# platform_smd2.net
KiCad netlist of a schematic drawn in EAGLE
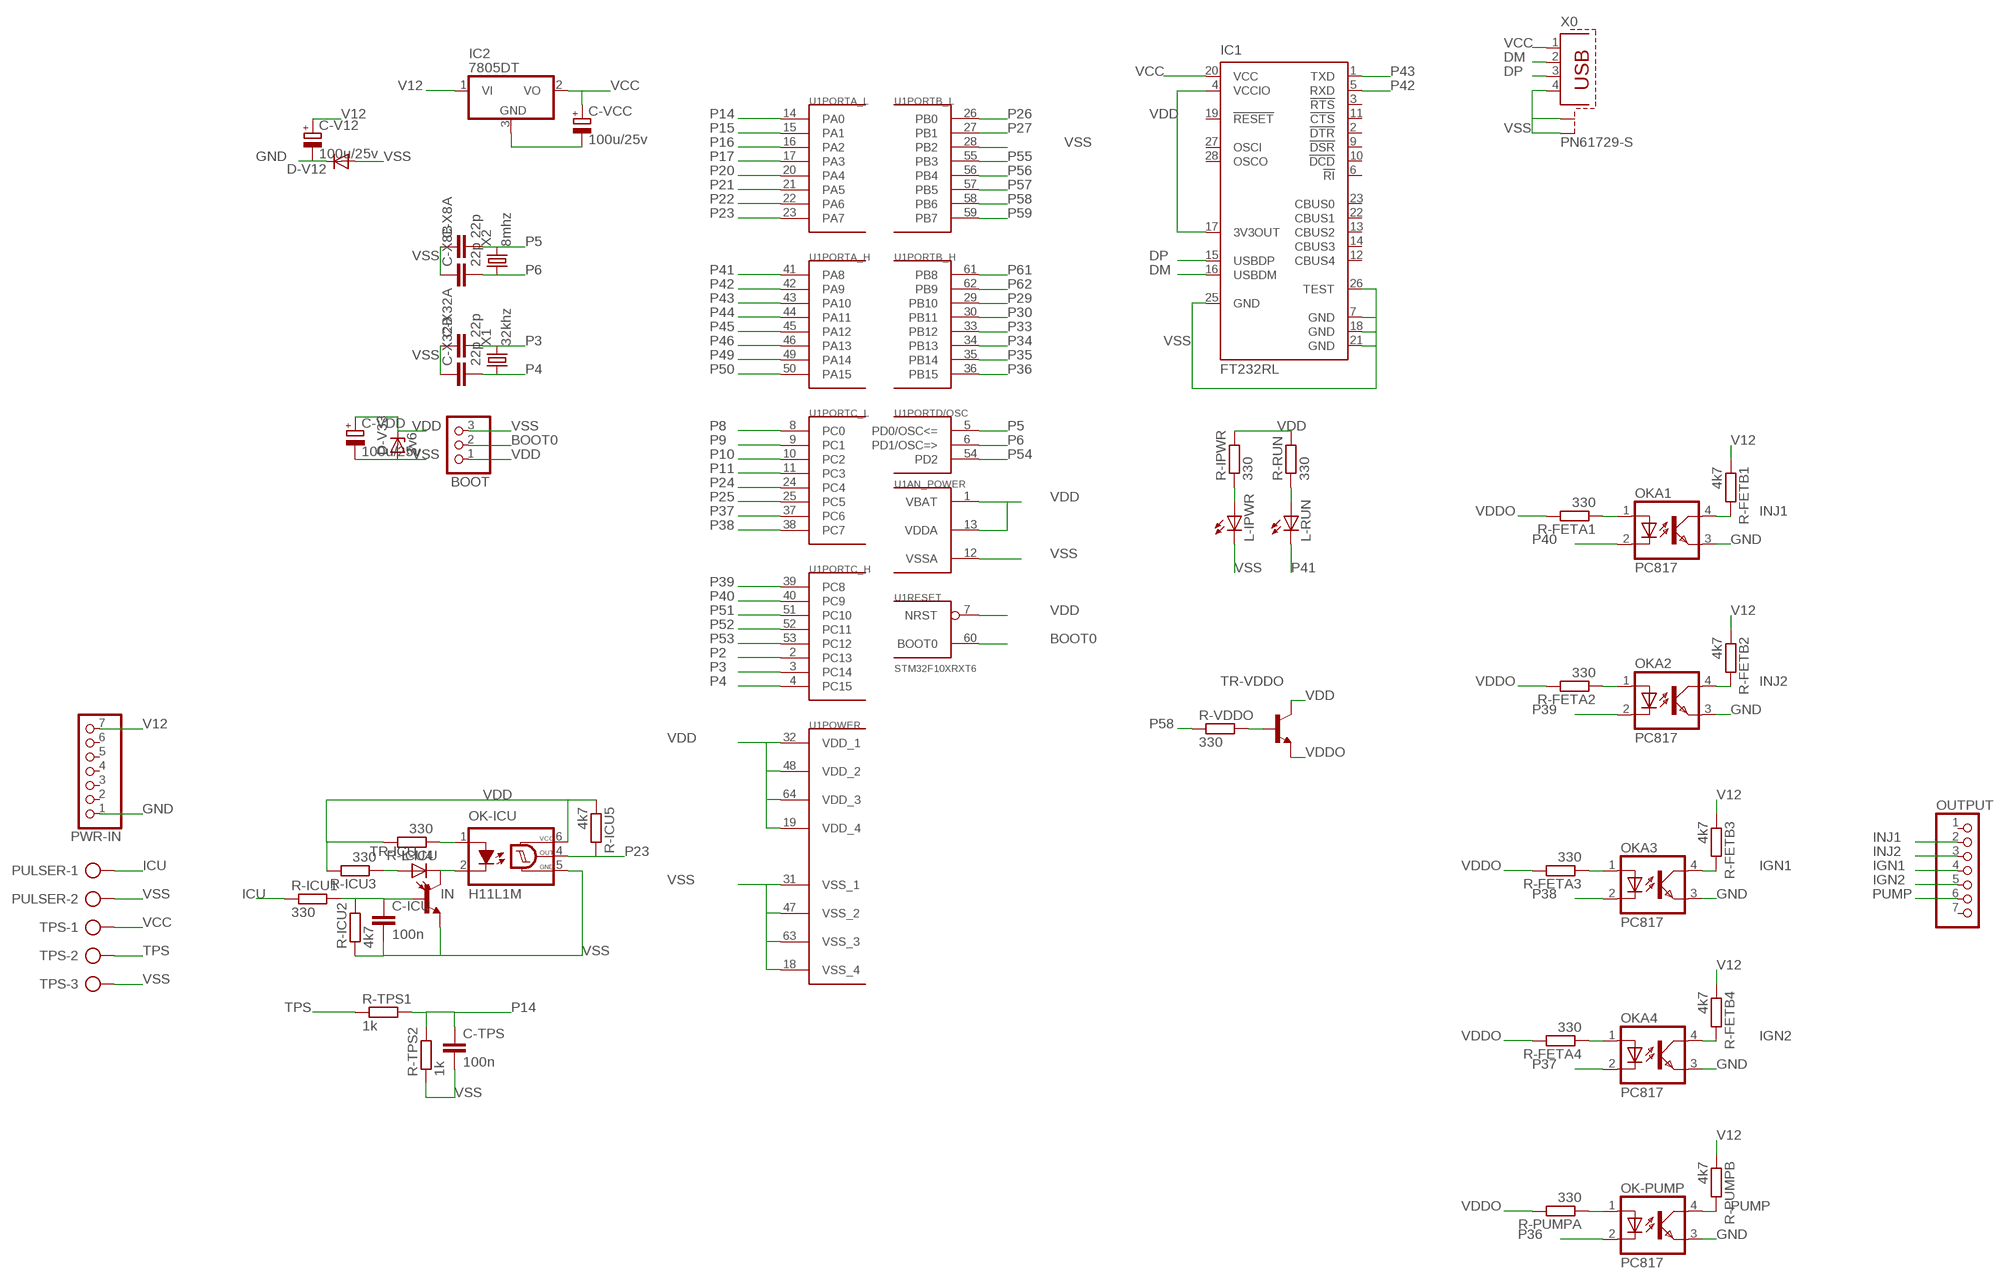
[diagram p0: schematic, sheet 1]

(export (version "E")
  (design (tool "Eeschema 10.0.6"))
  (components
    (comp (ref "BOOT")
      (value "PINHD-1X3")
      (footprint "eagle-import:1X03")
      (libsource (lib "eagle-import") (part "PINHD-1X3"))
    )
    (comp (ref "C-ICU")
      (value "100n")
      (footprint "eagle-import:C1206")
      (libsource (lib "eagle-import") (part "C-EUC1206"))
    )
    (comp (ref "C-TPS")
      (value "100n")
      (footprint "eagle-import:C1206")
      (libsource (lib "eagle-import") (part "C-EUC1206"))
    )
    (comp (ref "C-V12")
      (value "100u/25v")
      (footprint "eagle-import:PANASONIC_D")
      (libsource (lib "eagle-import") (part "CPOL-EUD"))
    )
    (comp (ref "C-VCC")
      (value "100u/25v")
      (footprint "eagle-import:PANASONIC_D")
      (libsource (lib "eagle-import") (part "CPOL-EUD"))
    )
    (comp (ref "C-VDD")
      (value "100u/25v")
      (footprint "eagle-import:PANASONIC_D")
      (libsource (lib "eagle-import") (part "CPOL-EUD"))
    )
    (comp (ref "C-X8A")
      (value "22p")
      (footprint "eagle-import:C1206")
      (libsource (lib "eagle-import") (part "C-EUC1206"))
    )
    (comp (ref "C-X8B")
      (value "22p")
      (footprint "eagle-import:C1206")
      (libsource (lib "eagle-import") (part "C-EUC1206"))
    )
    (comp (ref "C-X32A")
      (value "22p")
      (footprint "eagle-import:C1206")
      (libsource (lib "eagle-import") (part "C-EUC1206"))
    )
    (comp (ref "C-X32B")
      (value "22p")
      (footprint "eagle-import:C1206")
      (libsource (lib "eagle-import") (part "C-EUC1206"))
    )
    (comp (ref "D-V12")
      (value "DIODE-SMB")
      (footprint "eagle-import:SMB")
      (libsource (lib "eagle-import") (part "DIODE-SMB"))
    )
    (comp (ref "D-V33")
      (value "3v6")
      (footprint "eagle-import:SMB")
      (libsource (lib "eagle-import") (part "ZENER-DIODESMB"))
    )
    (comp (ref "IC1")
      (value "FT232RL")
      (footprint "eagle-import:SSOP28")
      (libsource (lib "eagle-import") (part "FT232RL"))
    )
    (comp (ref "IC2")
      (value "7805DT")
      (footprint "eagle-import:TO252")
      (libsource (lib "eagle-import") (part "78DT05"))
    )
    (comp (ref "L-ICU")
      (value "LEDSML0805")
      (footprint "eagle-import:SML0805")
      (libsource (lib "eagle-import") (part "LEDSML0805"))
    )
    (comp (ref "L-IPWR")
      (value "LEDSMT1206")
      (footprint "eagle-import:1206")
      (libsource (lib "eagle-import") (part "LEDSMT1206"))
    )
    (comp (ref "L-RUN")
      (value "LEDSMT1206")
      (footprint "eagle-import:1206")
      (libsource (lib "eagle-import") (part "LEDSMT1206"))
    )
    (comp (ref "OK-ICU")
      (value "H11L1M")
      (footprint "eagle-import:DIL06")
      (fields (field (name "MF") "FAIRCHILD SEMICONDUCTOR") (field (name "MPN") "H11L1-M"))
      (libsource (lib "eagle-import") (part "H11LM1"))
    )
    (comp (ref "OK-PUMP")
      (value "PC817")
      (footprint "eagle-import:DIL04")
      (fields (field (name "MPN") "PC817X4J000F"))
      (libsource (lib "eagle-import") (part "PC817"))
    )
    (comp (ref "OKA1")
      (value "PC817")
      (footprint "eagle-import:DIL04")
      (fields (field (name "MPN") "PC817X4J000F"))
      (libsource (lib "eagle-import") (part "PC817"))
    )
    (comp (ref "OKA2")
      (value "PC817")
      (footprint "eagle-import:DIL04")
      (fields (field (name "MPN") "PC817X4J000F"))
      (libsource (lib "eagle-import") (part "PC817"))
    )
    (comp (ref "OKA3")
      (value "PC817")
      (footprint "eagle-import:DIL04")
      (fields (field (name "MPN") "PC817X4J000F"))
      (libsource (lib "eagle-import") (part "PC817"))
    )
    (comp (ref "OKA4")
      (value "PC817")
      (footprint "eagle-import:DIL04")
      (fields (field (name "MPN") "PC817X4J000F"))
      (libsource (lib "eagle-import") (part "PC817"))
    )
    (comp (ref "OUTPUT")
      (value "PINHD-1X7")
      (footprint "eagle-import:1X07")
      (libsource (lib "eagle-import") (part "PINHD-1X7"))
    )
    (comp (ref "PULSER")
      (value "AK300/2")
      (footprint "eagle-import:AK300_2")
      (libsource (lib "eagle-import") (part "AK300/2"))
    )
    (comp (ref "PWR-IN")
      (value "PINHD-1X7")
      (footprint "eagle-import:1X07")
      (libsource (lib "eagle-import") (part "PINHD-1X7"))
    )
    (comp (ref "R-FETA1")
      (value "330")
      (footprint "eagle-import:R1206")
      (libsource (lib "eagle-import") (part "R-EU_R1206"))
    )
    (comp (ref "R-FETA2")
      (value "330")
      (footprint "eagle-import:R1206")
      (libsource (lib "eagle-import") (part "R-EU_R1206"))
    )
    (comp (ref "R-FETA3")
      (value "330")
      (footprint "eagle-import:R1206")
      (libsource (lib "eagle-import") (part "R-EU_R1206"))
    )
    (comp (ref "R-FETA4")
      (value "330")
      (footprint "eagle-import:R1206")
      (libsource (lib "eagle-import") (part "R-EU_R1206"))
    )
    (comp (ref "R-FETB1")
      (value "4k7")
      (footprint "eagle-import:R1206")
      (libsource (lib "eagle-import") (part "R-EU_R1206"))
    )
    (comp (ref "R-FETB2")
      (value "4k7")
      (footprint "eagle-import:R1206")
      (libsource (lib "eagle-import") (part "R-EU_R1206"))
    )
    (comp (ref "R-FETB3")
      (value "4k7")
      (footprint "eagle-import:R1206")
      (libsource (lib "eagle-import") (part "R-EU_R1206"))
    )
    (comp (ref "R-FETB4")
      (value "4k7")
      (footprint "eagle-import:R1206")
      (libsource (lib "eagle-import") (part "R-EU_R1206"))
    )
    (comp (ref "R-ICU1")
      (value "330")
      (footprint "eagle-import:R1206")
      (libsource (lib "eagle-import") (part "R-EU_R1206"))
    )
    (comp (ref "R-ICU2")
      (value "4k7")
      (footprint "eagle-import:R1206")
      (libsource (lib "eagle-import") (part "R-EU_R1206"))
    )
    (comp (ref "R-ICU3")
      (value "330")
      (footprint "eagle-import:R1206")
      (libsource (lib "eagle-import") (part "R-EU_R1206"))
    )
    (comp (ref "R-ICU4")
      (value "330")
      (footprint "eagle-import:R1206")
      (libsource (lib "eagle-import") (part "R-EU_R1206"))
    )
    (comp (ref "R-ICU5")
      (value "4k7")
      (footprint "eagle-import:R1206")
      (libsource (lib "eagle-import") (part "R-EU_R1206"))
    )
    (comp (ref "R-IPWR")
      (value "330")
      (footprint "eagle-import:R1206")
      (libsource (lib "eagle-import") (part "R-EU_R1206"))
    )
    (comp (ref "R-PUMPA")
      (value "330")
      (footprint "eagle-import:R1206")
      (libsource (lib "eagle-import") (part "R-EU_R1206"))
    )
    (comp (ref "R-PUMPB")
      (value "4k7")
      (footprint "eagle-import:R1206")
      (libsource (lib "eagle-import") (part "R-EU_R1206"))
    )
    (comp (ref "R-RUN")
      (value "330")
      (footprint "eagle-import:R1206")
      (libsource (lib "eagle-import") (part "R-EU_R1206"))
    )
    (comp (ref "R-TPS1")
      (value "1k")
      (footprint "eagle-import:R1206")
      (libsource (lib "eagle-import") (part "R-EU_R1206"))
    )
    (comp (ref "R-TPS2")
      (value "1k")
      (footprint "eagle-import:R1206")
      (libsource (lib "eagle-import") (part "R-EU_R1206"))
    )
    (comp (ref "R-VDDO")
      (value "330")
      (footprint "eagle-import:R0805")
      (libsource (lib "eagle-import") (part "R-EU_R0805"))
    )
    (comp (ref "TPS")
      (value "AK300/3")
      (footprint "eagle-import:AK300_3")
      (libsource (lib "eagle-import") (part "AK300/3"))
    )
    (comp (ref "TR-ICU")
      (value "MMBT3904LT1-NPN-SOT23-BEC")
      (footprint "eagle-import:SOT23-BEC")
      (libsource (lib "eagle-import") (part "-NPN-SOT23-BECMMBT3904LT1"))
    )
    (comp (ref "TR-VDDO")
      (value "MMBT3904LT1-NPN-SOT23-BEC")
      (footprint "eagle-import:SOT23-BEC")
      (libsource (lib "eagle-import") (part "-NPN-SOT23-BECMMBT3904LT1"))
    )
    (comp (ref "U1")
      (value "STM32F10XRXT6")
      (footprint "eagle-import:TQFP64")
      (libsource (lib "eagle-import") (part "STM32F10XRXT6"))
    )
    (comp (ref "X0")
      (value "PN61729-S")
      (footprint "eagle-import:PN61729-S")
      (libsource (lib "eagle-import") (part "PN61729-S"))
    )
    (comp (ref "X1")
      (value "32khz")
      (footprint "eagle-import:TC26V")
      (libsource (lib "eagle-import") (part "CRYSTALTC26V"))
    )
    (comp (ref "X2")
      (value "8mhz")
      (footprint "eagle-import:HC49U-V")
      (libsource (lib "eagle-import") (part "CRYSTALHC49U-V"))
    )
  )
  (nets
    (net (code "1") (name "/BOOT0") (class "Default")
      (node (ref "BOOT") (pin "2") (pinfunction "2_2") (pintype "passive"))
      (node (ref "U1") (pin "60") (pinfunction "BOOT0_60") (pintype "input"))
    )
    (net (code "2") (name "/DM") (class "Default")
      (node (ref "IC1") (pin "16") (pinfunction "USBDM_16") (pintype "bidirectional"))
      (node (ref "X0") (pin "2") (pinfunction "2_2") (pintype "passive"))
    )
    (net (code "3") (name "/DP") (class "Default")
      (node (ref "IC1") (pin "15") (pinfunction "USBDP_15") (pintype "bidirectional"))
      (node (ref "X0") (pin "3") (pinfunction "3_3") (pintype "passive"))
    )
    (net (code "4") (name "/GND") (class "Default")
      (node (ref "C-V12") (pin "-") (pinfunction "-_-") (pintype "passive"))
      (node (ref "D-V12") (pin "C") (pinfunction "C_C") (pintype "passive"))
      (node (ref "OK-PUMP") (pin "3") (pinfunction "EMIT_3") (pintype "passive"))
      (node (ref "OKA1") (pin "3") (pinfunction "EMIT_3") (pintype "passive"))
      (node (ref "OKA2") (pin "3") (pinfunction "EMIT_3") (pintype "passive"))
      (node (ref "OKA3") (pin "3") (pinfunction "EMIT_3") (pintype "passive"))
      (node (ref "OKA4") (pin "3") (pinfunction "EMIT_3") (pintype "passive"))
      (node (ref "PWR-IN") (pin "1") (pinfunction "1_1") (pintype "passive"))
    )
    (net (code "5") (name "/ICU") (class "Default")
      (node (ref "PULSER") (pin "1") (pinfunction "KL_1") (pintype "passive"))
      (node (ref "R-ICU1") (pin "1") (pinfunction "1_1") (pintype "passive"))
    )
    (net (code "6") (name "/IGN1") (class "Default")
      (node (ref "OKA3") (pin "4") (pinfunction "COL_4") (pintype "passive"))
      (node (ref "OUTPUT") (pin "4") (pinfunction "4_4") (pintype "passive"))
      (node (ref "R-FETB3") (pin "2") (pinfunction "2_2") (pintype "passive"))
    )
    (net (code "7") (name "/IGN2") (class "Default")
      (node (ref "OKA4") (pin "4") (pinfunction "COL_4") (pintype "passive"))
      (node (ref "OUTPUT") (pin "5") (pinfunction "5_5") (pintype "passive"))
      (node (ref "R-FETB4") (pin "2") (pinfunction "2_2") (pintype "passive"))
    )
    (net (code "8") (name "/IN") (class "Default")
      (node (ref "L-ICU") (pin "C") (pinfunction "C_C") (pintype "passive"))
      (node (ref "OK-ICU") (pin "2") (pinfunction "C_2") (pintype "passive"))
      (node (ref "TR-ICU") (pin "C") (pinfunction "C_C") (pintype "passive"))
    )
    (net (code "9") (name "/INJ1") (class "Default")
      (node (ref "OKA1") (pin "4") (pinfunction "COL_4") (pintype "passive"))
      (node (ref "OUTPUT") (pin "2") (pinfunction "2_2") (pintype "passive"))
      (node (ref "R-FETB1") (pin "2") (pinfunction "2_2") (pintype "passive"))
    )
    (net (code "10") (name "/INJ2") (class "Default")
      (node (ref "OKA2") (pin "4") (pinfunction "COL_4") (pintype "passive"))
      (node (ref "OUTPUT") (pin "3") (pinfunction "3_3") (pintype "passive"))
      (node (ref "R-FETB2") (pin "2") (pinfunction "2_2") (pintype "passive"))
    )
    (net (code "11") (name "/P2") (class "Default")
      (node (ref "U1") (pin "2") (pinfunction "PC13_2") (pintype "bidirectional"))
    )
    (net (code "12") (name "/P3") (class "Default")
      (node (ref "C-X32A") (pin "2") (pinfunction "2_2") (pintype "passive"))
      (node (ref "U1") (pin "3") (pinfunction "PC14_3") (pintype "bidirectional"))
      (node (ref "X1") (pin "2") (pinfunction "2_2") (pintype "passive"))
    )
    (net (code "13") (name "/P4") (class "Default")
      (node (ref "C-X32B") (pin "2") (pinfunction "2_2") (pintype "passive"))
      (node (ref "U1") (pin "4") (pinfunction "PC15_4") (pintype "bidirectional"))
      (node (ref "X1") (pin "1") (pinfunction "1_1") (pintype "passive"))
    )
    (net (code "14") (name "/P5") (class "Default")
      (node (ref "C-X8A") (pin "2") (pinfunction "2_2") (pintype "passive"))
      (node (ref "U1") (pin "5") (pinfunction "PD0/OSC<=_5") (pintype "bidirectional"))
      (node (ref "X2") (pin "2") (pinfunction "2_2") (pintype "passive"))
    )
    (net (code "15") (name "/P6") (class "Default")
      (node (ref "C-X8B") (pin "2") (pinfunction "2_2") (pintype "passive"))
      (node (ref "U1") (pin "6") (pinfunction "PD1/OSC=>_6") (pintype "bidirectional"))
      (node (ref "X2") (pin "1") (pinfunction "1_1") (pintype "passive"))
    )
    (net (code "16") (name "/P8") (class "Default")
      (node (ref "U1") (pin "8") (pinfunction "PC0_8") (pintype "bidirectional"))
    )
    (net (code "17") (name "/P9") (class "Default")
      (node (ref "U1") (pin "9") (pinfunction "PC1_9") (pintype "bidirectional"))
    )
    (net (code "18") (name "/P10") (class "Default")
      (node (ref "U1") (pin "10") (pinfunction "PC2_10") (pintype "bidirectional"))
    )
    (net (code "19") (name "/P11") (class "Default")
      (node (ref "U1") (pin "11") (pinfunction "PC3_11") (pintype "bidirectional"))
    )
    (net (code "20") (name "/P14") (class "Default")
      (node (ref "C-TPS") (pin "1") (pinfunction "1_1") (pintype "passive"))
      (node (ref "R-TPS1") (pin "2") (pinfunction "2_2") (pintype "passive"))
      (node (ref "R-TPS2") (pin "2") (pinfunction "2_2") (pintype "passive"))
      (node (ref "U1") (pin "14") (pinfunction "PA0_14") (pintype "bidirectional"))
    )
    (net (code "21") (name "/P15") (class "Default")
      (node (ref "U1") (pin "15") (pinfunction "PA1_15") (pintype "bidirectional"))
    )
    (net (code "22") (name "/P16") (class "Default")
      (node (ref "U1") (pin "16") (pinfunction "PA2_16") (pintype "bidirectional"))
    )
    (net (code "23") (name "/P17") (class "Default")
      (node (ref "U1") (pin "17") (pinfunction "PA3_17") (pintype "bidirectional"))
    )
    (net (code "24") (name "/P20") (class "Default")
      (node (ref "U1") (pin "20") (pinfunction "PA4_20") (pintype "bidirectional"))
    )
    (net (code "25") (name "/P21") (class "Default")
      (node (ref "U1") (pin "21") (pinfunction "PA5_21") (pintype "bidirectional"))
    )
    (net (code "26") (name "/P22") (class "Default")
      (node (ref "U1") (pin "22") (pinfunction "PA6_22") (pintype "bidirectional"))
    )
    (net (code "27") (name "/P23") (class "Default")
      (node (ref "OK-ICU") (pin "4") (pinfunction "OUT_4") (pintype "output"))
      (node (ref "R-ICU5") (pin "2") (pinfunction "2_2") (pintype "passive"))
      (node (ref "U1") (pin "23") (pinfunction "PA7_23") (pintype "bidirectional"))
    )
    (net (code "28") (name "/P24") (class "Default")
      (node (ref "U1") (pin "24") (pinfunction "PC4_24") (pintype "bidirectional"))
    )
    (net (code "29") (name "/P25") (class "Default")
      (node (ref "U1") (pin "25") (pinfunction "PC5_25") (pintype "bidirectional"))
    )
    (net (code "30") (name "/P26") (class "Default")
      (node (ref "U1") (pin "26") (pinfunction "PB0_26") (pintype "bidirectional"))
    )
    (net (code "31") (name "/P27") (class "Default")
      (node (ref "U1") (pin "27") (pinfunction "PB1_27") (pintype "bidirectional"))
    )
    (net (code "32") (name "/P29") (class "Default")
      (node (ref "U1") (pin "29") (pinfunction "PB10_29") (pintype "bidirectional"))
    )
    (net (code "33") (name "/P30") (class "Default")
      (node (ref "U1") (pin "30") (pinfunction "PB11_30") (pintype "bidirectional"))
    )
    (net (code "34") (name "/P33") (class "Default")
      (node (ref "U1") (pin "33") (pinfunction "PB12_33") (pintype "bidirectional"))
    )
    (net (code "35") (name "/P34") (class "Default")
      (node (ref "U1") (pin "34") (pinfunction "PB13_34") (pintype "bidirectional"))
    )
    (net (code "36") (name "/P35") (class "Default")
      (node (ref "U1") (pin "35") (pinfunction "PB14_35") (pintype "bidirectional"))
    )
    (net (code "37") (name "/P36") (class "Default")
      (node (ref "OK-PUMP") (pin "2") (pinfunction "C_2") (pintype "passive"))
      (node (ref "U1") (pin "36") (pinfunction "PB15_36") (pintype "bidirectional"))
    )
    (net (code "38") (name "/P37") (class "Default")
      (node (ref "OKA4") (pin "2") (pinfunction "C_2") (pintype "passive"))
      (node (ref "U1") (pin "37") (pinfunction "PC6_37") (pintype "bidirectional"))
    )
    (net (code "39") (name "/P38") (class "Default")
      (node (ref "OKA3") (pin "2") (pinfunction "C_2") (pintype "passive"))
      (node (ref "U1") (pin "38") (pinfunction "PC7_38") (pintype "bidirectional"))
    )
    (net (code "40") (name "/P39") (class "Default")
      (node (ref "OKA2") (pin "2") (pinfunction "C_2") (pintype "passive"))
      (node (ref "U1") (pin "39") (pinfunction "PC8_39") (pintype "bidirectional"))
    )
    (net (code "41") (name "/P40") (class "Default")
      (node (ref "OKA1") (pin "2") (pinfunction "C_2") (pintype "passive"))
      (node (ref "U1") (pin "40") (pinfunction "PC9_40") (pintype "bidirectional"))
    )
    (net (code "42") (name "/P41") (class "Default")
      (node (ref "L-RUN") (pin "C") (pinfunction "C_C") (pintype "passive"))
      (node (ref "U1") (pin "41") (pinfunction "PA8_41") (pintype "bidirectional"))
    )
    (net (code "43") (name "/P42") (class "Default")
      (node (ref "IC1") (pin "5") (pinfunction "RXD_5") (pintype "input"))
      (node (ref "U1") (pin "42") (pinfunction "PA9_42") (pintype "bidirectional"))
    )
    (net (code "44") (name "/P43") (class "Default")
      (node (ref "IC1") (pin "1") (pinfunction "TXD_1") (pintype "output"))
      (node (ref "U1") (pin "43") (pinfunction "PA10_43") (pintype "bidirectional"))
    )
    (net (code "45") (name "/P44") (class "Default")
      (node (ref "U1") (pin "44") (pinfunction "PA11_44") (pintype "bidirectional"))
    )
    (net (code "46") (name "/P45") (class "Default")
      (node (ref "U1") (pin "45") (pinfunction "PA12_45") (pintype "bidirectional"))
    )
    (net (code "47") (name "/P46") (class "Default")
      (node (ref "U1") (pin "46") (pinfunction "PA13_46") (pintype "bidirectional"))
    )
    (net (code "48") (name "/P49") (class "Default")
      (node (ref "U1") (pin "49") (pinfunction "PA14_49") (pintype "bidirectional"))
    )
    (net (code "49") (name "/P50") (class "Default")
      (node (ref "U1") (pin "50") (pinfunction "PA15_50") (pintype "bidirectional"))
    )
    (net (code "50") (name "/P51") (class "Default")
      (node (ref "U1") (pin "51") (pinfunction "PC10_51") (pintype "bidirectional"))
    )
    (net (code "51") (name "/P52") (class "Default")
      (node (ref "U1") (pin "52") (pinfunction "PC11_52") (pintype "bidirectional"))
    )
    (net (code "52") (name "/P53") (class "Default")
      (node (ref "U1") (pin "53") (pinfunction "PC12_53") (pintype "bidirectional"))
    )
    (net (code "53") (name "/P54") (class "Default")
      (node (ref "U1") (pin "54") (pinfunction "PD2_54") (pintype "bidirectional"))
    )
    (net (code "54") (name "/P55") (class "Default")
      (node (ref "U1") (pin "55") (pinfunction "PB3_55") (pintype "bidirectional"))
    )
    (net (code "55") (name "/P56") (class "Default")
      (node (ref "U1") (pin "56") (pinfunction "PB4_56") (pintype "bidirectional"))
    )
    (net (code "56") (name "/P57") (class "Default")
      (node (ref "U1") (pin "57") (pinfunction "PB5_57") (pintype "bidirectional"))
    )
    (net (code "57") (name "/P58") (class "Default")
      (node (ref "R-VDDO") (pin "1") (pinfunction "1_1") (pintype "passive"))
      (node (ref "U1") (pin "58") (pinfunction "PB6_58") (pintype "bidirectional"))
    )
    (net (code "58") (name "/P59") (class "Default")
      (node (ref "U1") (pin "59") (pinfunction "PB7_59") (pintype "bidirectional"))
    )
    (net (code "59") (name "/P61") (class "Default")
      (node (ref "U1") (pin "61") (pinfunction "PB8_61") (pintype "bidirectional"))
    )
    (net (code "60") (name "/P62") (class "Default")
      (node (ref "U1") (pin "62") (pinfunction "PB9_62") (pintype "bidirectional"))
    )
    (net (code "61") (name "/PUMP") (class "Default")
      (node (ref "OK-PUMP") (pin "4") (pinfunction "COL_4") (pintype "passive"))
      (node (ref "OUTPUT") (pin "6") (pinfunction "6_6") (pintype "passive"))
      (node (ref "R-PUMPB") (pin "2") (pinfunction "2_2") (pintype "passive"))
    )
    (net (code "62") (name "/TPS") (class "Default")
      (node (ref "R-TPS1") (pin "1") (pinfunction "1_1") (pintype "passive"))
      (node (ref "TPS") (pin "2") (pinfunction "KL_2") (pintype "passive"))
    )
    (net (code "63") (name "/V12") (class "Default")
      (node (ref "C-V12") (pin "+") (pinfunction "+_+") (pintype "passive"))
      (node (ref "IC2") (pin "1") (pinfunction "VI_1") (pintype "input"))
      (node (ref "PWR-IN") (pin "7") (pinfunction "7_7") (pintype "passive"))
      (node (ref "R-FETB1") (pin "1") (pinfunction "1_1") (pintype "passive"))
      (node (ref "R-FETB2") (pin "1") (pinfunction "1_1") (pintype "passive"))
      (node (ref "R-FETB3") (pin "1") (pinfunction "1_1") (pintype "passive"))
      (node (ref "R-FETB4") (pin "1") (pinfunction "1_1") (pintype "passive"))
      (node (ref "R-PUMPB") (pin "1") (pinfunction "1_1") (pintype "passive"))
    )
    (net (code "64") (name "/VCC") (class "Default")
      (node (ref "C-VCC") (pin "+") (pinfunction "+_+") (pintype "passive"))
      (node (ref "IC1") (pin "20") (pinfunction "VCC_20") (pintype "power_in"))
      (node (ref "IC2") (pin "2") (pinfunction "VO_2") (pintype "passive"))
      (node (ref "TPS") (pin "1") (pinfunction "KL_1") (pintype "passive"))
      (node (ref "X0") (pin "1") (pinfunction "1_1") (pintype "passive"))
    )
    (net (code "65") (name "/VDD") (class "Default")
      (node (ref "BOOT") (pin "1") (pinfunction "1_1") (pintype "passive"))
      (node (ref "C-VDD") (pin "+") (pinfunction "+_+") (pintype "passive"))
      (node (ref "D-V33") (pin "C") (pinfunction "C_C") (pintype "passive"))
      (node (ref "IC1") (pin "17") (pinfunction "3V3OUT_17") (pintype "output"))
      (node (ref "IC1") (pin "4") (pinfunction "VCCIO_4") (pintype "power_in"))
      (node (ref "OK-ICU") (pin "6") (pinfunction "VCC_6") (pintype "power_in"))
      (node (ref "R-ICU3") (pin "2") (pinfunction "2_2") (pintype "passive"))
      (node (ref "R-ICU4") (pin "2") (pinfunction "2_2") (pintype "passive"))
      (node (ref "R-ICU5") (pin "1") (pinfunction "1_1") (pintype "passive"))
      (node (ref "R-IPWR") (pin "2") (pinfunction "2_2") (pintype "passive"))
      (node (ref "R-RUN") (pin "2") (pinfunction "2_2") (pintype "passive"))
      (node (ref "TR-VDDO") (pin "C") (pinfunction "C_C") (pintype "passive"))
      (node (ref "U1") (pin "1") (pinfunction "VBAT_1") (pintype "power_in"))
      (node (ref "U1") (pin "13") (pinfunction "VDDA_13") (pintype "power_in"))
      (node (ref "U1") (pin "19") (pinfunction "VDD_4_19") (pintype "power_in"))
      (node (ref "U1") (pin "32") (pinfunction "VDD_1_32") (pintype "power_in"))
      (node (ref "U1") (pin "48") (pinfunction "VDD_2_48") (pintype "power_in"))
      (node (ref "U1") (pin "64") (pinfunction "VDD_3_64") (pintype "power_in"))
      (node (ref "U1") (pin "7") (pinfunction "NRST_7") (pintype "input"))
    )
    (net (code "66") (name "/VDDO") (class "Default")
      (node (ref "R-FETA1") (pin "2") (pinfunction "2_2") (pintype "passive"))
      (node (ref "R-FETA2") (pin "2") (pinfunction "2_2") (pintype "passive"))
      (node (ref "R-FETA3") (pin "2") (pinfunction "2_2") (pintype "passive"))
      (node (ref "R-FETA4") (pin "2") (pinfunction "2_2") (pintype "passive"))
      (node (ref "R-PUMPA") (pin "2") (pinfunction "2_2") (pintype "passive"))
      (node (ref "TR-VDDO") (pin "E") (pinfunction "E_E") (pintype "passive"))
    )
    (net (code "67") (name "/VSS") (class "Default")
      (node (ref "BOOT") (pin "3") (pinfunction "3_3") (pintype "passive"))
      (node (ref "C-ICU") (pin "2") (pinfunction "2_2") (pintype "passive"))
      (node (ref "C-TPS") (pin "2") (pinfunction "2_2") (pintype "passive"))
      (node (ref "C-VCC") (pin "-") (pinfunction "-_-") (pintype "passive"))
      (node (ref "C-VDD") (pin "-") (pinfunction "-_-") (pintype "passive"))
      (node (ref "C-X32A") (pin "1") (pinfunction "1_1") (pintype "passive"))
      (node (ref "C-X32B") (pin "1") (pinfunction "1_1") (pintype "passive"))
      (node (ref "C-X8A") (pin "1") (pinfunction "1_1") (pintype "passive"))
      (node (ref "C-X8B") (pin "1") (pinfunction "1_1") (pintype "passive"))
      (node (ref "D-V12") (pin "A") (pinfunction "A_A") (pintype "passive"))
      (node (ref "D-V33") (pin "A") (pinfunction "A_A") (pintype "passive"))
      (node (ref "IC1") (pin "18") (pinfunction "GND_18") (pintype "power_in"))
      (node (ref "IC1") (pin "21") (pinfunction "GND_21") (pintype "power_in"))
      (node (ref "IC1") (pin "25") (pinfunction "GND_25") (pintype "power_in"))
      (node (ref "IC1") (pin "26") (pinfunction "TEST_26") (pintype "input"))
      (node (ref "IC1") (pin "7") (pinfunction "GND_7") (pintype "power_in"))
      (node (ref "IC2") (pin "3") (pinfunction "GND_3") (pintype "passive"))
      (node (ref "L-IPWR") (pin "C") (pinfunction "C_C") (pintype "passive"))
      (node (ref "OK-ICU") (pin "5") (pinfunction "GND_5") (pintype "power_in"))
      (node (ref "PULSER") (pin "2") (pinfunction "KL_2") (pintype "passive"))
      (node (ref "R-ICU2") (pin "1") (pinfunction "1_1") (pintype "passive"))
      (node (ref "R-TPS2") (pin "1") (pinfunction "1_1") (pintype "passive"))
      (node (ref "TPS") (pin "3") (pinfunction "KL_3") (pintype "passive"))
      (node (ref "TR-ICU") (pin "E") (pinfunction "E_E") (pintype "passive"))
      (node (ref "U1") (pin "12") (pinfunction "VSSA_12") (pintype "power_in"))
      (node (ref "U1") (pin "18") (pinfunction "VSS_4_18") (pintype "power_in"))
      (node (ref "U1") (pin "28") (pinfunction "PB2_28") (pintype "bidirectional"))
      (node (ref "U1") (pin "31") (pinfunction "VSS_1_31") (pintype "power_in"))
      (node (ref "U1") (pin "47") (pinfunction "VSS_2_47") (pintype "power_in"))
      (node (ref "U1") (pin "63") (pinfunction "VSS_3_63") (pintype "power_in"))
      (node (ref "X0") (pin "4") (pinfunction "4_4") (pintype "passive"))
      (node (ref "X0") (pin "S1") (pinfunction "S1_S1") (pintype "passive"))
      (node (ref "X0") (pin "S2") (pinfunction "S2_S2") (pintype "passive"))
    )
    (net (code "68") (name "Net-(C-ICU-Pad1)") (class "Default")
      (node (ref "C-ICU") (pin "1") (pinfunction "1_1") (pintype "passive"))
      (node (ref "R-ICU1") (pin "2") (pinfunction "2_2") (pintype "passive"))
      (node (ref "R-ICU2") (pin "2") (pinfunction "2_2") (pintype "passive"))
      (node (ref "TR-ICU") (pin "B") (pinfunction "B_B") (pintype "passive"))
    )
    (net (code "69") (name "Net-(L-ICU-PadA)") (class "Default")
      (node (ref "L-ICU") (pin "A") (pinfunction "A_A") (pintype "passive"))
      (node (ref "R-ICU3") (pin "1") (pinfunction "1_1") (pintype "passive"))
    )
    (net (code "70") (name "Net-(L-IPWR-PadA)") (class "Default")
      (node (ref "L-IPWR") (pin "A") (pinfunction "A_A") (pintype "passive"))
      (node (ref "R-IPWR") (pin "1") (pinfunction "1_1") (pintype "passive"))
    )
    (net (code "71") (name "Net-(L-RUN-PadA)") (class "Default")
      (node (ref "L-RUN") (pin "A") (pinfunction "A_A") (pintype "passive"))
      (node (ref "R-RUN") (pin "1") (pinfunction "1_1") (pintype "passive"))
    )
    (net (code "72") (name "Net-(OK-ICU-A)") (class "Default")
      (node (ref "OK-ICU") (pin "1") (pinfunction "A_1") (pintype "passive"))
      (node (ref "R-ICU4") (pin "1") (pinfunction "1_1") (pintype "passive"))
    )
    (net (code "73") (name "Net-(OK-PUMP-A)") (class "Default")
      (node (ref "OK-PUMP") (pin "1") (pinfunction "A_1") (pintype "passive"))
      (node (ref "R-PUMPA") (pin "1") (pinfunction "1_1") (pintype "passive"))
    )
    (net (code "74") (name "Net-(OKA1-A)") (class "Default")
      (node (ref "OKA1") (pin "1") (pinfunction "A_1") (pintype "passive"))
      (node (ref "R-FETA1") (pin "1") (pinfunction "1_1") (pintype "passive"))
    )
    (net (code "75") (name "Net-(OKA2-A)") (class "Default")
      (node (ref "OKA2") (pin "1") (pinfunction "A_1") (pintype "passive"))
      (node (ref "R-FETA2") (pin "1") (pinfunction "1_1") (pintype "passive"))
    )
    (net (code "76") (name "Net-(OKA3-A)") (class "Default")
      (node (ref "OKA3") (pin "1") (pinfunction "A_1") (pintype "passive"))
      (node (ref "R-FETA3") (pin "1") (pinfunction "1_1") (pintype "passive"))
    )
    (net (code "77") (name "Net-(OKA4-A)") (class "Default")
      (node (ref "OKA4") (pin "1") (pinfunction "A_1") (pintype "passive"))
      (node (ref "R-FETA4") (pin "1") (pinfunction "1_1") (pintype "passive"))
    )
    (net (code "78") (name "Net-(R-VDDO-Pad2)") (class "Default")
      (node (ref "R-VDDO") (pin "2") (pinfunction "2_2") (pintype "passive"))
      (node (ref "TR-VDDO") (pin "B") (pinfunction "B_B") (pintype "passive"))
    )
    (net (code "79") (name "unconnected-(IC1-CBUS0-Pad23)") (class "Default")
      (node (ref "IC1") (pin "23") (pinfunction "CBUS0_23") (pintype "bidirectional"))
    )
    (net (code "80") (name "unconnected-(IC1-CBUS1-Pad22)") (class "Default")
      (node (ref "IC1") (pin "22") (pinfunction "CBUS1_22") (pintype "bidirectional"))
    )
    (net (code "81") (name "unconnected-(IC1-CBUS2-Pad13)") (class "Default")
      (node (ref "IC1") (pin "13") (pinfunction "CBUS2_13") (pintype "bidirectional"))
    )
    (net (code "82") (name "unconnected-(IC1-CBUS3-Pad14)") (class "Default")
      (node (ref "IC1") (pin "14") (pinfunction "CBUS3_14") (pintype "bidirectional"))
    )
    (net (code "83") (name "unconnected-(IC1-CBUS4-Pad12)") (class "Default")
      (node (ref "IC1") (pin "12") (pinfunction "CBUS4_12") (pintype "bidirectional"))
    )
    (net (code "84") (name "unconnected-(IC1-OSCI-Pad27)") (class "Default")
      (node (ref "IC1") (pin "27") (pinfunction "OSCI_27") (pintype "input"))
    )
    (net (code "85") (name "unconnected-(IC1-OSCO-Pad28)") (class "Default")
      (node (ref "IC1") (pin "28") (pinfunction "OSCO_28") (pintype "output"))
    )
    (net (code "86") (name "unconnected-(IC1-~{CTS}-Pad11)") (class "Default")
      (node (ref "IC1") (pin "11") (pinfunction "~{CTS}_11") (pintype "input"))
    )
    (net (code "87") (name "unconnected-(IC1-~{DCD}-Pad10)") (class "Default")
      (node (ref "IC1") (pin "10") (pinfunction "~{DCD}_10") (pintype "input"))
    )
    (net (code "88") (name "unconnected-(IC1-~{DSR}-Pad9)") (class "Default")
      (node (ref "IC1") (pin "9") (pinfunction "~{DSR}_9") (pintype "input"))
    )
    (net (code "89") (name "unconnected-(IC1-~{DTR}-Pad2)") (class "Default")
      (node (ref "IC1") (pin "2") (pinfunction "~{DTR}_2") (pintype "output"))
    )
    (net (code "90") (name "unconnected-(IC1-~{RESET}-Pad19)") (class "Default")
      (node (ref "IC1") (pin "19") (pinfunction "~{RESET}_19") (pintype "input"))
    )
    (net (code "91") (name "unconnected-(IC1-~{RI}-Pad6)") (class "Default")
      (node (ref "IC1") (pin "6") (pinfunction "~{RI}_6") (pintype "input"))
    )
    (net (code "92") (name "unconnected-(IC1-~{RTS}-Pad3)") (class "Default")
      (node (ref "IC1") (pin "3") (pinfunction "~{RTS}_3") (pintype "output"))
    )
    (net (code "93") (name "unconnected-(OUTPUT-Pad1)") (class "Default")
      (node (ref "OUTPUT") (pin "1") (pinfunction "1_1") (pintype "passive"))
    )
    (net (code "94") (name "unconnected-(OUTPUT-Pad7)") (class "Default")
      (node (ref "OUTPUT") (pin "7") (pinfunction "7_7") (pintype "passive"))
    )
    (net (code "95") (name "unconnected-(PWR-IN-Pad2)") (class "Default")
      (node (ref "PWR-IN") (pin "2") (pinfunction "2_2") (pintype "passive"))
    )
    (net (code "96") (name "unconnected-(PWR-IN-Pad3)") (class "Default")
      (node (ref "PWR-IN") (pin "3") (pinfunction "3_3") (pintype "passive"))
    )
    (net (code "97") (name "unconnected-(PWR-IN-Pad4)") (class "Default")
      (node (ref "PWR-IN") (pin "4") (pinfunction "4_4") (pintype "passive"))
    )
    (net (code "98") (name "unconnected-(PWR-IN-Pad5)") (class "Default")
      (node (ref "PWR-IN") (pin "5") (pinfunction "5_5") (pintype "passive"))
    )
    (net (code "99") (name "unconnected-(PWR-IN-Pad6)") (class "Default")
      (node (ref "PWR-IN") (pin "6") (pinfunction "6_6") (pintype "passive"))
    )
  )
)
